# xnor.net
KiCad netlist of a schematic drawn in EAGLE
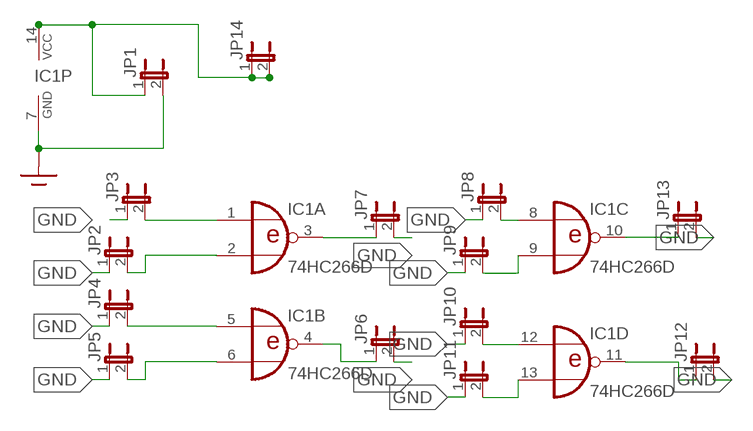
[diagram p0: schematic, sheet 1]

(export (version "E")
  (design (tool "Eeschema 10.0.6"))
  (components
    (comp (ref "IC1")
      (value "74HC266D")
      (footprint "eagle-import:SO14")
      (libsource (lib "eagle-import") (part "74266DHC"))
    )
    (comp (ref "JP1")
      (value "JP1E")
      (footprint "eagle-import:JP1")
      (libsource (lib "eagle-import") (part "JP1E"))
    )
    (comp (ref "JP2")
      (value "JP1E")
      (footprint "eagle-import:JP1")
      (libsource (lib "eagle-import") (part "JP1E"))
    )
    (comp (ref "JP3")
      (value "JP1E")
      (footprint "eagle-import:JP1")
      (libsource (lib "eagle-import") (part "JP1E"))
    )
    (comp (ref "JP4")
      (value "JP1E")
      (footprint "eagle-import:JP1")
      (libsource (lib "eagle-import") (part "JP1E"))
    )
    (comp (ref "JP5")
      (value "JP1E")
      (footprint "eagle-import:JP1")
      (libsource (lib "eagle-import") (part "JP1E"))
    )
    (comp (ref "JP6")
      (value "JP1E")
      (footprint "eagle-import:JP1")
      (libsource (lib "eagle-import") (part "JP1E"))
    )
    (comp (ref "JP7")
      (value "JP1E")
      (footprint "eagle-import:JP1")
      (libsource (lib "eagle-import") (part "JP1E"))
    )
    (comp (ref "JP8")
      (value "JP1E")
      (footprint "eagle-import:JP1")
      (libsource (lib "eagle-import") (part "JP1E"))
    )
    (comp (ref "JP9")
      (value "JP1E")
      (footprint "eagle-import:JP1")
      (libsource (lib "eagle-import") (part "JP1E"))
    )
    (comp (ref "JP10")
      (value "JP1E")
      (footprint "eagle-import:JP1")
      (libsource (lib "eagle-import") (part "JP1E"))
    )
    (comp (ref "JP11")
      (value "JP1E")
      (footprint "eagle-import:JP1")
      (libsource (lib "eagle-import") (part "JP1E"))
    )
    (comp (ref "JP12")
      (value "JP1E")
      (footprint "eagle-import:JP1")
      (libsource (lib "eagle-import") (part "JP1E"))
    )
    (comp (ref "JP13")
      (value "JP1E")
      (footprint "eagle-import:JP1")
      (libsource (lib "eagle-import") (part "JP1E"))
    )
    (comp (ref "JP14")
      (value "JP1E")
      (footprint "eagle-import:JP1")
      (libsource (lib "eagle-import") (part "JP1E"))
    )
  )
  (nets
    (net (code "1") (name "GND") (class "Default")
      (node (ref "IC1") (pin "7") (pinfunction "GND_7") (pintype "power_in"))
      (node (ref "JP1") (pin "2") (pinfunction "2_2") (pintype "passive"))
      (node (ref "JP10") (pin "1") (pinfunction "1_1") (pintype "passive"))
      (node (ref "JP11") (pin "1") (pinfunction "1_1") (pintype "passive"))
      (node (ref "JP12") (pin "2") (pinfunction "2_2") (pintype "passive"))
      (node (ref "JP13") (pin "2") (pinfunction "2_2") (pintype "passive"))
      (node (ref "JP2") (pin "1") (pinfunction "1_1") (pintype "passive"))
      (node (ref "JP3") (pin "1") (pinfunction "1_1") (pintype "passive"))
      (node (ref "JP4") (pin "1") (pinfunction "1_1") (pintype "passive"))
      (node (ref "JP5") (pin "1") (pinfunction "1_1") (pintype "passive"))
      (node (ref "JP6") (pin "2") (pinfunction "2_2") (pintype "passive"))
      (node (ref "JP7") (pin "2") (pinfunction "2_2") (pintype "passive"))
      (node (ref "JP8") (pin "1") (pinfunction "1_1") (pintype "passive"))
      (node (ref "JP9") (pin "1") (pinfunction "1_1") (pintype "passive"))
    )
    (net (code "2") (name "Net-(IC1A-I0)") (class "Default")
      (node (ref "IC1") (pin "1") (pinfunction "I0_1") (pintype "input"))
      (node (ref "JP3") (pin "2") (pinfunction "2_2") (pintype "passive"))
    )
    (net (code "3") (name "Net-(IC1A-I1)") (class "Default")
      (node (ref "IC1") (pin "2") (pinfunction "I1_2") (pintype "input"))
      (node (ref "JP2") (pin "2") (pinfunction "2_2") (pintype "passive"))
    )
    (net (code "4") (name "Net-(IC1A-O)") (class "Default")
      (node (ref "IC1") (pin "3") (pinfunction "O_3") (pintype "open_collector"))
      (node (ref "JP7") (pin "1") (pinfunction "1_1") (pintype "passive"))
    )
    (net (code "5") (name "Net-(IC1B-I0)") (class "Default")
      (node (ref "IC1") (pin "5") (pinfunction "I0_5") (pintype "input"))
      (node (ref "JP4") (pin "2") (pinfunction "2_2") (pintype "passive"))
    )
    (net (code "6") (name "Net-(IC1B-I1)") (class "Default")
      (node (ref "IC1") (pin "6") (pinfunction "I1_6") (pintype "input"))
      (node (ref "JP5") (pin "2") (pinfunction "2_2") (pintype "passive"))
    )
    (net (code "7") (name "Net-(IC1B-O)") (class "Default")
      (node (ref "IC1") (pin "4") (pinfunction "O_4") (pintype "open_collector"))
      (node (ref "JP6") (pin "1") (pinfunction "1_1") (pintype "passive"))
    )
    (net (code "8") (name "Net-(IC1C-I0)") (class "Default")
      (node (ref "IC1") (pin "8") (pinfunction "I0_8") (pintype "input"))
      (node (ref "JP8") (pin "2") (pinfunction "2_2") (pintype "passive"))
    )
    (net (code "9") (name "Net-(IC1C-I1)") (class "Default")
      (node (ref "IC1") (pin "9") (pinfunction "I1_9") (pintype "input"))
      (node (ref "JP9") (pin "2") (pinfunction "2_2") (pintype "passive"))
    )
    (net (code "10") (name "Net-(IC1C-O)") (class "Default")
      (node (ref "IC1") (pin "10") (pinfunction "O_10") (pintype "open_collector"))
      (node (ref "JP13") (pin "1") (pinfunction "1_1") (pintype "passive"))
    )
    (net (code "11") (name "Net-(IC1D-I0)") (class "Default")
      (node (ref "IC1") (pin "12") (pinfunction "I0_12") (pintype "input"))
      (node (ref "JP10") (pin "2") (pinfunction "2_2") (pintype "passive"))
    )
    (net (code "12") (name "Net-(IC1D-I1)") (class "Default")
      (node (ref "IC1") (pin "13") (pinfunction "I1_13") (pintype "input"))
      (node (ref "JP11") (pin "2") (pinfunction "2_2") (pintype "passive"))
    )
    (net (code "13") (name "Net-(IC1D-O)") (class "Default")
      (node (ref "IC1") (pin "11") (pinfunction "O_11") (pintype "open_collector"))
      (node (ref "JP12") (pin "1") (pinfunction "1_1") (pintype "passive"))
    )
    (net (code "14") (name "Net-(IC1E-VCC)") (class "Default")
      (node (ref "IC1") (pin "14") (pinfunction "VCC_14") (pintype "power_in"))
      (node (ref "JP1") (pin "1") (pinfunction "1_1") (pintype "passive"))
      (node (ref "JP14") (pin "1") (pinfunction "1_1") (pintype "passive"))
      (node (ref "JP14") (pin "2") (pinfunction "2_2") (pintype "passive"))
    )
  )
)
